# FPGA.net
KiCad netlist of a schematic drawn in Altium Designer
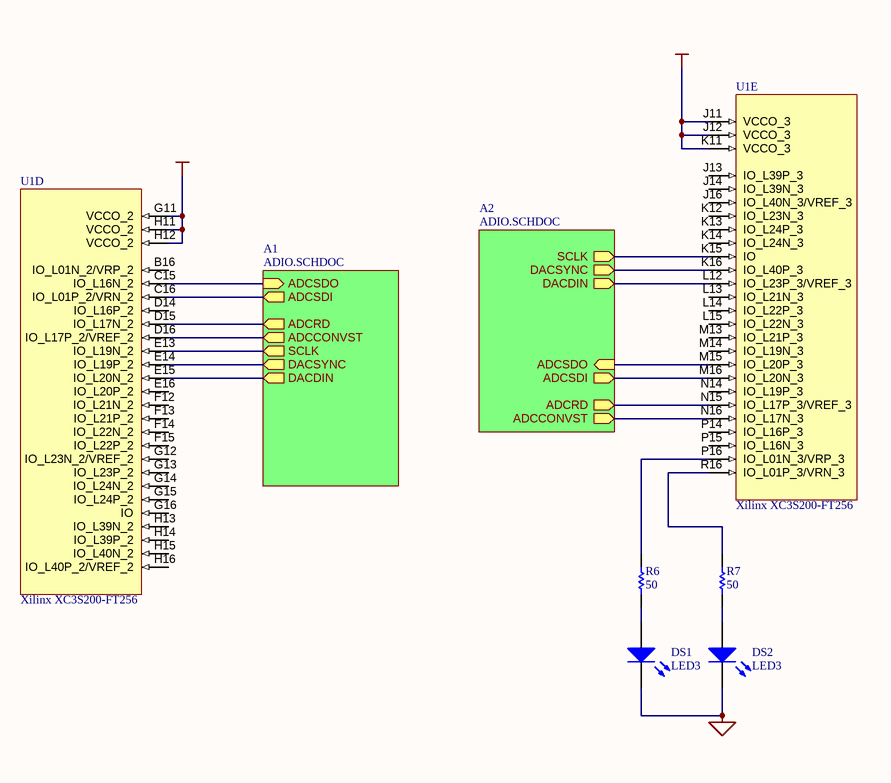
[diagram p0: FPGA.SCHDOC]

(export (version "E")
  (design (tool "Eeschema 10.0.6"))
  (components
    (comp (ref "DS1")
      (value "LED3")
      (footprint "SMD _LED")
      (description "Typical BLUE SiC LED")
      (fields (field (name "PUBLISHER") "Altium Limited"))
      (libsource (lib "Miscellaneous Devices") (part "LED3"))
    )
    (comp (ref "DS2")
      (value "LED3")
      (footprint "SMD _LED")
      (description "Typical BLUE SiC LED")
      (fields (field (name "PUBLISHER") "Altium Limited"))
      (libsource (lib "Miscellaneous Devices") (part "LED3"))
    )
    (comp (ref "R6")
      (value "50")
      (footprint "0603")
      (description "Standard Passive Resistor")
      (fields (field (name "Comment") "current-limiting series res"))
      (libsource (lib "parts") (part "RESISTOR"))
    )
    (comp (ref "R7")
      (value "50")
      (footprint "0603")
      (description "Standard Passive Resistor")
      (fields (field (name "Comment") "current-limiting series res"))
      (libsource (lib "parts") (part "RESISTOR"))
    )
    (comp (ref "U1")
      (value "Xilinx XC3S200-FT256")
      (footprint "Xilinx FT256 BGA")
      (description "Xilinx Spartan-3 FPGA")
      (libsource (lib "") (part "XC3S200-FT256_1"))
    )
  )
  (nets
    (net (code "1") (name "/ADCCONVST") (class "Default")
      (node (ref "U1") (pin "N16") (pinfunction "IO_L17N_3_N16") (pintype "input"))
    )
    (net (code "2") (name "/ADCCONVST_1") (class "Default")
      (node (ref "U1") (pin "D16") (pinfunction "IO_L17P_2/VREF_2_D16") (pintype "input"))
    )
    (net (code "3") (name "/ADCRD") (class "Default")
      (node (ref "U1") (pin "N15") (pinfunction "IO_L17P_3/VREF_3_N15") (pintype "input"))
    )
    (net (code "4") (name "/ADCRD_1") (class "Default")
      (node (ref "U1") (pin "D15") (pinfunction "IO_L17N_2_D15") (pintype "input"))
    )
    (net (code "5") (name "/ADCSDI") (class "Default")
      (node (ref "U1") (pin "M16") (pinfunction "IO_L20N_3_M16") (pintype "input"))
    )
    (net (code "6") (name "/ADCSDI_1") (class "Default")
      (node (ref "U1") (pin "C16") (pinfunction "IO_L01P_2/VRN_2_C16") (pintype "input"))
    )
    (net (code "7") (name "/ADCSDO") (class "Default")
      (node (ref "U1") (pin "M15") (pinfunction "IO_L20P_3_M15") (pintype "input"))
    )
    (net (code "8") (name "/ADCSDO_1") (class "Default")
      (node (ref "U1") (pin "C15") (pinfunction "IO_L16N_2_C15") (pintype "input"))
    )
    (net (code "9") (name "/DACDIN") (class "Default")
      (node (ref "U1") (pin "L12") (pinfunction "IO_L23P_3/VREF_3_L12") (pintype "input"))
    )
    (net (code "10") (name "/DACDIN_1") (class "Default")
      (node (ref "U1") (pin "E15") (pinfunction "IO_L20N_2_E15") (pintype "input"))
    )
    (net (code "11") (name "/DACSYNC") (class "Default")
      (node (ref "U1") (pin "K16") (pinfunction "IO_L40P_3_K16") (pintype "input"))
    )
    (net (code "12") (name "/DACSYNC_1") (class "Default")
      (node (ref "U1") (pin "E14") (pinfunction "IO_L19P_2_E14") (pintype "input"))
    )
    (net (code "13") (name "/SCLK") (class "Default")
      (node (ref "U1") (pin "K15") (pinfunction "IO_K15") (pintype "input"))
    )
    (net (code "14") (name "/SCLK_1") (class "Default")
      (node (ref "U1") (pin "E13") (pinfunction "IO_L19N_2_E13") (pintype "input"))
    )
    (net (code "15") (name "GND") (class "Default")
      (node (ref "DS1") (pin "2") (pinfunction "K_2") (pintype "passive"))
      (node (ref "DS2") (pin "2") (pinfunction "K_2") (pintype "passive"))
    )
    (net (code "16") (name "Net-(DS1-A)") (class "Default")
      (node (ref "DS1") (pin "1") (pinfunction "A_1") (pintype "passive"))
      (node (ref "R6") (pin "2") (pintype "passive"))
    )
    (net (code "17") (name "Net-(DS2-A)") (class "Default")
      (node (ref "DS2") (pin "1") (pinfunction "A_1") (pintype "passive"))
      (node (ref "R7") (pin "2") (pintype "passive"))
    )
    (net (code "18") (name "Net-(U1E-IO_L01N_3{slash}VRP_3)") (class "Default")
      (node (ref "R6") (pin "1") (pintype "passive"))
      (node (ref "U1") (pin "P16") (pinfunction "IO_L01N_3/VRP_3_P16") (pintype "input"))
    )
    (net (code "19") (name "Net-(U1E-IO_L01P_3{slash}VRN_3)") (class "Default")
      (node (ref "R7") (pin "1") (pintype "passive"))
      (node (ref "U1") (pin "R16") (pinfunction "IO_L01P_3/VRN_3_R16") (pintype "input"))
    )
    (net (code "20") (name "VCC") (class "Default")
      (node (ref "U1") (pin "G11") (pinfunction "VCCO_2_G11") (pintype "input"))
      (node (ref "U1") (pin "H11") (pinfunction "VCCO_2_H11") (pintype "input"))
      (node (ref "U1") (pin "H12") (pinfunction "VCCO_2_H12") (pintype "input"))
      (node (ref "U1") (pin "J11") (pinfunction "VCCO_3_J11") (pintype "input"))
      (node (ref "U1") (pin "J12") (pinfunction "VCCO_3_J12") (pintype "input"))
      (node (ref "U1") (pin "K11") (pinfunction "VCCO_3_K11") (pintype "input"))
    )
    (net (code "21") (name "unconnected-(U1D-IO-PadG16)") (class "Default")
      (node (ref "U1") (pin "G16") (pinfunction "IO_G16") (pintype "input"))
    )
    (net (code "22") (name "unconnected-(U1D-IO_L01N_2{slash}VRP_2-PadB16)") (class "Default")
      (node (ref "U1") (pin "B16") (pinfunction "IO_L01N_2/VRP_2_B16") (pintype "input"))
    )
    (net (code "23") (name "unconnected-(U1D-IO_L16P_2-PadD14)") (class "Default")
      (node (ref "U1") (pin "D14") (pinfunction "IO_L16P_2_D14") (pintype "input"))
    )
    (net (code "24") (name "unconnected-(U1D-IO_L20P_2-PadE16)") (class "Default")
      (node (ref "U1") (pin "E16") (pinfunction "IO_L20P_2_E16") (pintype "input"))
    )
    (net (code "25") (name "unconnected-(U1D-IO_L21N_2-PadF12)") (class "Default")
      (node (ref "U1") (pin "F12") (pinfunction "IO_L21N_2_F12") (pintype "input"))
    )
    (net (code "26") (name "unconnected-(U1D-IO_L21P_2-PadF13)") (class "Default")
      (node (ref "U1") (pin "F13") (pinfunction "IO_L21P_2_F13") (pintype "input"))
    )
    (net (code "27") (name "unconnected-(U1D-IO_L22N_2-PadF14)") (class "Default")
      (node (ref "U1") (pin "F14") (pinfunction "IO_L22N_2_F14") (pintype "input"))
    )
    (net (code "28") (name "unconnected-(U1D-IO_L22P_2-PadF15)") (class "Default")
      (node (ref "U1") (pin "F15") (pinfunction "IO_L22P_2_F15") (pintype "input"))
    )
    (net (code "29") (name "unconnected-(U1D-IO_L23N_2{slash}VREF_2-PadG12)") (class "Default")
      (node (ref "U1") (pin "G12") (pinfunction "IO_L23N_2/VREF_2_G12") (pintype "input"))
    )
    (net (code "30") (name "unconnected-(U1D-IO_L23P_2-PadG13)") (class "Default")
      (node (ref "U1") (pin "G13") (pinfunction "IO_L23P_2_G13") (pintype "input"))
    )
    (net (code "31") (name "unconnected-(U1D-IO_L24N_2-PadG14)") (class "Default")
      (node (ref "U1") (pin "G14") (pinfunction "IO_L24N_2_G14") (pintype "input"))
    )
    (net (code "32") (name "unconnected-(U1D-IO_L24P_2-PadG15)") (class "Default")
      (node (ref "U1") (pin "G15") (pinfunction "IO_L24P_2_G15") (pintype "input"))
    )
    (net (code "33") (name "unconnected-(U1D-IO_L39N_2-PadH13)") (class "Default")
      (node (ref "U1") (pin "H13") (pinfunction "IO_L39N_2_H13") (pintype "input"))
    )
    (net (code "34") (name "unconnected-(U1D-IO_L39P_2-PadH14)") (class "Default")
      (node (ref "U1") (pin "H14") (pinfunction "IO_L39P_2_H14") (pintype "input"))
    )
    (net (code "35") (name "unconnected-(U1D-IO_L40N_2-PadH15)") (class "Default")
      (node (ref "U1") (pin "H15") (pinfunction "IO_L40N_2_H15") (pintype "input"))
    )
    (net (code "36") (name "unconnected-(U1D-IO_L40P_2{slash}VREF_2-PadH16)") (class "Default")
      (node (ref "U1") (pin "H16") (pinfunction "IO_L40P_2/VREF_2_H16") (pintype "input"))
    )
    (net (code "37") (name "unconnected-(U1E-IO_L16N_3-PadP15)") (class "Default")
      (node (ref "U1") (pin "P15") (pinfunction "IO_L16N_3_P15") (pintype "input"))
    )
    (net (code "38") (name "unconnected-(U1E-IO_L16P_3-PadP14)") (class "Default")
      (node (ref "U1") (pin "P14") (pinfunction "IO_L16P_3_P14") (pintype "input"))
    )
    (net (code "39") (name "unconnected-(U1E-IO_L19N_3-PadM14)") (class "Default")
      (node (ref "U1") (pin "M14") (pinfunction "IO_L19N_3_M14") (pintype "input"))
    )
    (net (code "40") (name "unconnected-(U1E-IO_L19P_3-PadN14)") (class "Default")
      (node (ref "U1") (pin "N14") (pinfunction "IO_L19P_3_N14") (pintype "input"))
    )
    (net (code "41") (name "unconnected-(U1E-IO_L21N_3-PadL13)") (class "Default")
      (node (ref "U1") (pin "L13") (pinfunction "IO_L21N_3_L13") (pintype "input"))
    )
    (net (code "42") (name "unconnected-(U1E-IO_L21P_3-PadM13)") (class "Default")
      (node (ref "U1") (pin "M13") (pinfunction "IO_L21P_3_M13") (pintype "input"))
    )
    (net (code "43") (name "unconnected-(U1E-IO_L22N_3-PadL15)") (class "Default")
      (node (ref "U1") (pin "L15") (pinfunction "IO_L22N_3_L15") (pintype "input"))
    )
    (net (code "44") (name "unconnected-(U1E-IO_L22P_3-PadL14)") (class "Default")
      (node (ref "U1") (pin "L14") (pinfunction "IO_L22P_3_L14") (pintype "input"))
    )
    (net (code "45") (name "unconnected-(U1E-IO_L23N_3-PadK12)") (class "Default")
      (node (ref "U1") (pin "K12") (pinfunction "IO_L23N_3_K12") (pintype "input"))
    )
    (net (code "46") (name "unconnected-(U1E-IO_L24N_3-PadK14)") (class "Default")
      (node (ref "U1") (pin "K14") (pinfunction "IO_L24N_3_K14") (pintype "input"))
    )
    (net (code "47") (name "unconnected-(U1E-IO_L24P_3-PadK13)") (class "Default")
      (node (ref "U1") (pin "K13") (pinfunction "IO_L24P_3_K13") (pintype "input"))
    )
    (net (code "48") (name "unconnected-(U1E-IO_L39N_3-PadJ14)") (class "Default")
      (node (ref "U1") (pin "J14") (pinfunction "IO_L39N_3_J14") (pintype "input"))
    )
    (net (code "49") (name "unconnected-(U1E-IO_L39P_3-PadJ13)") (class "Default")
      (node (ref "U1") (pin "J13") (pinfunction "IO_L39P_3_J13") (pintype "input"))
    )
    (net (code "50") (name "unconnected-(U1E-IO_L40N_3{slash}VREF_3-PadJ16)") (class "Default")
      (node (ref "U1") (pin "J16") (pinfunction "IO_L40N_3/VREF_3_J16") (pintype "input"))
    )
  )
)
